# Pixie85Servo.net
KiCad netlist of a schematic drawn in EAGLE
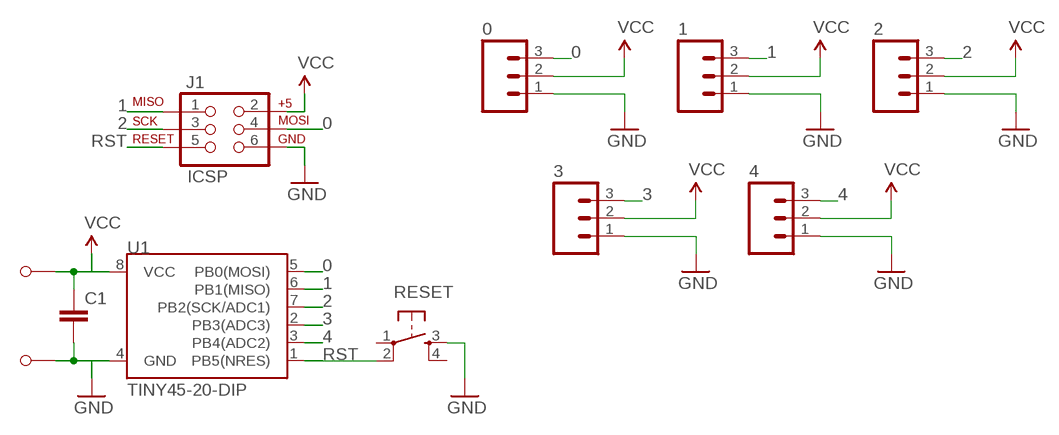
[diagram p0: schematic, sheet 1]

(export (version "E")
  (design (tool "Eeschema 10.0.6"))
  (components
    (comp (ref "+")
      (value "M1")
      (footprint "eagle-import:M1_NO_STRAIN")
      (libsource (lib "eagle-import") (part "M1"))
    )
    (comp (ref "-")
      (value "M1")
      (footprint "eagle-import:M1_NO_STRAIN")
      (libsource (lib "eagle-import") (part "M1"))
    )
    (comp (ref "0")
      (value "M03PTH")
      (footprint "eagle-import:1X03")
      (libsource (lib "eagle-import") (part "M03PTH"))
    )
    (comp (ref "1")
      (value "M03PTH")
      (footprint "eagle-import:1X03")
      (libsource (lib "eagle-import") (part "M03PTH"))
    )
    (comp (ref "2")
      (value "M03PTH")
      (footprint "eagle-import:1X03")
      (libsource (lib "eagle-import") (part "M03PTH"))
    )
    (comp (ref "3")
      (value "M03PTH")
      (footprint "eagle-import:1X03")
      (libsource (lib "eagle-import") (part "M03PTH"))
    )
    (comp (ref "4")
      (value "M03PTH")
      (footprint "eagle-import:1X03")
      (libsource (lib "eagle-import") (part "M03PTH"))
    )
    (comp (ref "C1")
      (value "CAPPTH")
      (footprint "eagle-import:CAP-PTH-SMALL")
      (libsource (lib "eagle-import") (part "CAPPTH"))
    )
    (comp (ref "J1")
      (value "ICSP")
      (footprint "eagle-import:2X3-NS")
      (libsource (lib "eagle-import") (part "AVR_SPI_PRG_6LABELED"))
    )
    (comp (ref "RESET")
      (value "TAC_SWITCHPTH")
      (footprint "eagle-import:TACTILE-PTH")
      (libsource (lib "eagle-import") (part "TAC_SWITCHPTH"))
    )
    (comp (ref "U1")
      (value "TINY45-20-DIP")
      (footprint "eagle-import:DIP08")
      (libsource (lib "eagle-import") (part "ATTINY45TINY45-20-DIP"))
    )
  )
  (nets
    (net (code "1") (name "/0") (class "Default")
      (node (ref "0") (pin "3") (pinfunction "3_3") (pintype "passive"))
      (node (ref "J1") (pin "4") (pinfunction "MOSI_4") (pintype "passive"))
      (node (ref "U1") (pin "5") (pinfunction "PB0(MOSI)_5") (pintype "bidirectional"))
    )
    (net (code "2") (name "/1") (class "Default")
      (node (ref "1") (pin "3") (pinfunction "3_3") (pintype "passive"))
      (node (ref "J1") (pin "1") (pinfunction "MISO_1") (pintype "passive"))
      (node (ref "U1") (pin "6") (pinfunction "PB1(MISO)_6") (pintype "bidirectional"))
    )
    (net (code "3") (name "/2") (class "Default")
      (node (ref "2") (pin "3") (pinfunction "3_3") (pintype "passive"))
      (node (ref "J1") (pin "3") (pinfunction "SCK_3") (pintype "passive"))
      (node (ref "U1") (pin "7") (pinfunction "PB2(SCK/ADC1)_7") (pintype "bidirectional"))
    )
    (net (code "4") (name "/3") (class "Default")
      (node (ref "3") (pin "3") (pinfunction "3_3") (pintype "passive"))
      (node (ref "U1") (pin "2") (pinfunction "PB3(ADC3)_2") (pintype "bidirectional"))
    )
    (net (code "5") (name "/4") (class "Default")
      (node (ref "4") (pin "3") (pinfunction "3_3") (pintype "passive"))
      (node (ref "U1") (pin "3") (pinfunction "PB4(ADC2)_3") (pintype "bidirectional"))
    )
    (net (code "6") (name "/RST") (class "Default")
      (node (ref "J1") (pin "5") (pinfunction "RST_5") (pintype "passive"))
      (node (ref "RESET") (pin "2") (pinfunction "2_2") (pintype "passive"))
      (node (ref "U1") (pin "1") (pinfunction "PB5(NRES)_1") (pintype "bidirectional"))
    )
    (net (code "7") (name "GND") (class "Default")
      (node (ref "-") (pin "P$1") (pinfunction "P$1_P$1") (pintype "bidirectional"))
      (node (ref "0") (pin "1") (pinfunction "1_1") (pintype "passive"))
      (node (ref "1") (pin "1") (pinfunction "1_1") (pintype "passive"))
      (node (ref "2") (pin "1") (pinfunction "1_1") (pintype "passive"))
      (node (ref "3") (pin "1") (pinfunction "1_1") (pintype "passive"))
      (node (ref "4") (pin "1") (pinfunction "1_1") (pintype "passive"))
      (node (ref "C1") (pin "2") (pinfunction "2_2") (pintype "passive"))
      (node (ref "J1") (pin "6") (pinfunction "GND_6") (pintype "passive"))
      (node (ref "RESET") (pin "3") (pinfunction "3_3") (pintype "passive"))
      (node (ref "U1") (pin "4") (pinfunction "GND_4") (pintype "bidirectional"))
    )
    (net (code "8") (name "VCC") (class "Default")
      (node (ref "+") (pin "P$1") (pinfunction "P$1_P$1") (pintype "bidirectional"))
      (node (ref "0") (pin "2") (pinfunction "2_2") (pintype "passive"))
      (node (ref "1") (pin "2") (pinfunction "2_2") (pintype "passive"))
      (node (ref "2") (pin "2") (pinfunction "2_2") (pintype "passive"))
      (node (ref "3") (pin "2") (pinfunction "2_2") (pintype "passive"))
      (node (ref "4") (pin "2") (pinfunction "2_2") (pintype "passive"))
      (node (ref "C1") (pin "1") (pinfunction "1_1") (pintype "passive"))
      (node (ref "J1") (pin "2") (pinfunction "V+_2") (pintype "passive"))
      (node (ref "U1") (pin "8") (pinfunction "VCC_8") (pintype "bidirectional"))
    )
    (net (code "9") (name "unconnected-(RESET-Pad1)") (class "Default")
      (node (ref "RESET") (pin "1") (pinfunction "1_1") (pintype "passive"))
    )
    (net (code "10") (name "unconnected-(RESET-Pad4)") (class "Default")
      (node (ref "RESET") (pin "4") (pinfunction "4_4") (pintype "passive"))
    )
  )
)
